# 48V_0_5A_Converter.net
KiCad netlist of a schematic drawn in Altium Designer
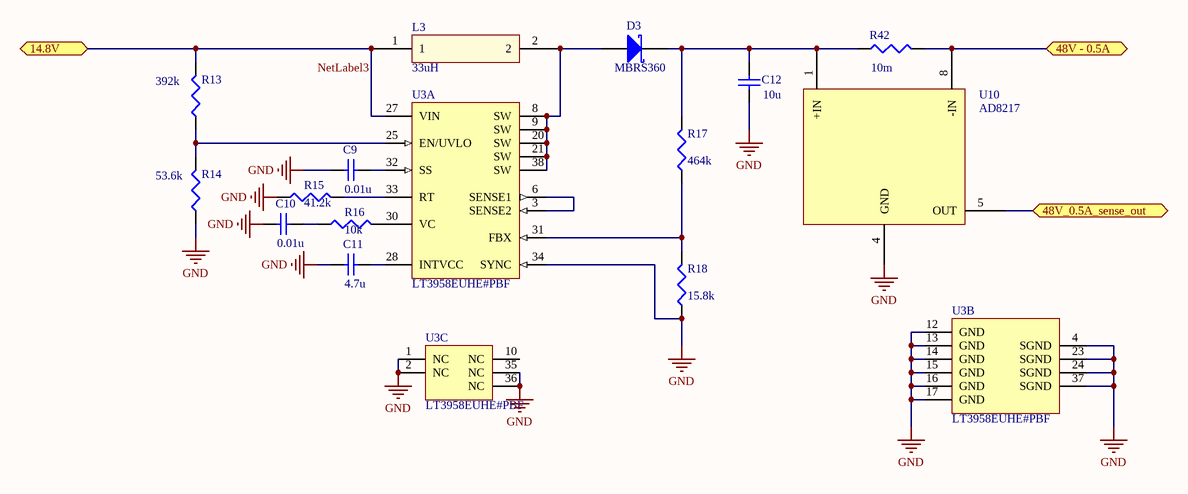
[diagram p0: 48V_0.5A_Converter.SchDoc]

(export (version "E")
  (design (tool "Eeschema 10.0.6"))
  (components
    (comp (ref "C9")
      (value "0.01u")
      (footprint "C1206")
      (description "Capacitor (Semiconductor SIM Model)")
      (fields (field (name "Comment") "Cap Semi") (field (name "PUBLISHER") "Altium Limited"))
      (libsource (lib "Miscellaneous Devices") (part "Cap Semi"))
    )
    (comp (ref "C10")
      (value "0.01u")
      (footprint "C1206")
      (description "Capacitor (Semiconductor SIM Model)")
      (fields (field (name "Comment") "Cap Semi") (field (name "PUBLISHER") "Altium Limited"))
      (libsource (lib "Miscellaneous Devices") (part "Cap Semi"))
    )
    (comp (ref "C11")
      (value "4.7u")
      (footprint "C1206")
      (description "Capacitor (Semiconductor SIM Model)")
      (fields (field (name "Comment") "Cap Semi") (field (name "PUBLISHER") "Altium Limited"))
      (libsource (lib "Miscellaneous Devices") (part "Cap Semi"))
    )
    (comp (ref "C12")
      (value "10u")
      (footprint "C1206")
      (description "Capacitor (Semiconductor SIM Model)")
      (fields (field (name "Comment") "Cap Semi") (field (name "PUBLISHER") "Altium Limited"))
      (libsource (lib "Miscellaneous Devices") (part "Cap Semi"))
    )
    (comp (ref "D3")
      (value "MBRS360")
      (footprint "SMB")
      (description "Schottky Diode")
      (fields (field (name "PUBLISHER") "Altium Limited"))
      (libsource (lib "Miscellaneous Devices") (part "D Schottky"))
    )
    (comp (ref "L3")
      (value "33uH")
      (footprint "INDP125125X45N")
      (description "33uH Inductors")
      (libsource (lib "IHLP-6767DZ-11") (part "IHLP-6767DZ-11"))
    )
    (comp (ref "R13")
      (value "392k")
      (footprint "J1-0603")
      (description "Resistor")
      (fields (field (name "Comment") "Res3") (field (name "PUBLISHER") "Altium Limited"))
      (libsource (lib "Miscellaneous Devices") (part "Res3"))
    )
    (comp (ref "R14")
      (value "53.6k")
      (footprint "J1-0603")
      (description "Resistor")
      (fields (field (name "Comment") "Res3") (field (name "PUBLISHER") "Altium Limited"))
      (libsource (lib "Miscellaneous Devices") (part "Res3"))
    )
    (comp (ref "R15")
      (value "41.2k")
      (footprint "J1-0603")
      (description "Resistor")
      (fields (field (name "Comment") "Res3") (field (name "PUBLISHER") "Altium Limited"))
      (libsource (lib "Miscellaneous Devices") (part "Res3"))
    )
    (comp (ref "R16")
      (value "10k")
      (footprint "J1-0603")
      (description "Resistor")
      (fields (field (name "Comment") "Res3") (field (name "PUBLISHER") "Altium Limited"))
      (libsource (lib "Miscellaneous Devices") (part "Res3"))
    )
    (comp (ref "R17")
      (value "464k")
      (footprint "J1-0603")
      (description "Resistor")
      (fields (field (name "Comment") "Res3") (field (name "PUBLISHER") "Altium Limited"))
      (libsource (lib "Miscellaneous Devices") (part "Res3"))
    )
    (comp (ref "R18")
      (value "15.8k")
      (footprint "J1-0603")
      (description "Resistor")
      (fields (field (name "Comment") "Res3") (field (name "PUBLISHER") "Altium Limited"))
      (libsource (lib "Miscellaneous Devices") (part "Res3"))
    )
    (comp (ref "R42")
      (value "10m")
      (footprint "J1-0603")
      (description "Resistor")
      (fields (field (name "Comment") "Res3") (field (name "PUBLISHER") "Altium Limited"))
      (libsource (lib "Miscellaneous Devices") (part "Res3"))
    )
    (comp (ref "U3")
      (value "LT3958EUHE#PBF")
      (footprint "LT-UHE-36-V-UHE28MA_V")
      (fields (field (name "MANUFACTURER") "Linear Technology"))
      (libsource (lib "Linear Technology Power Management Switching Regulator LT1074-LT8705") (part "LT3958EUHE#PBF"))
    )
    (comp (ref "U10")
      (value "AD8217")
      (footprint "TSOP65P490X110-8N")
      (description "Current Shunt Moniter")
      (libsource (lib "AD8217") (part "Component_1"))
    )
  )
  (nets
    (net (code "1") (name "/14.8V") (class "Default")
      (node (ref "L3") (pin "1") (pinfunction "1_1") (pintype "passive"))
      (node (ref "R13") (pin "2") (pinfunction "2_2") (pintype "passive"))
      (node (ref "U3") (pin "27") (pinfunction "VIN_27") (pintype "power_in"))
    )
    (net (code "2") (name "/48V - 0.5A") (class "Default")
      (node (ref "R42") (pin "2") (pinfunction "2_2") (pintype "passive"))
      (node (ref "U10") (pin "8") (pinfunction "-IN_8") (pintype "passive"))
    )
    (net (code "3") (name "/48V_0.5A_sense_out") (class "Default")
      (node (ref "U10") (pin "5") (pinfunction "OUT_5") (pintype "passive"))
    )
    (net (code "5") (name "GND") (class "Default")
      (node (ref "C10") (pin "1") (pinfunction "1_1") (pintype "passive"))
      (node (ref "C11") (pin "1") (pinfunction "1_1") (pintype "passive"))
      (node (ref "C12") (pin "1") (pinfunction "1_1") (pintype "passive"))
      (node (ref "C9") (pin "1") (pinfunction "1_1") (pintype "passive"))
      (node (ref "R14") (pin "1") (pinfunction "1_1") (pintype "passive"))
      (node (ref "R15") (pin "1") (pinfunction "1_1") (pintype "passive"))
      (node (ref "R18") (pin "1") (pinfunction "1_1") (pintype "passive"))
      (node (ref "U10") (pin "4") (pinfunction "GND_4") (pintype "passive"))
      (node (ref "U3") (pin "1") (pinfunction "NC_1") (pintype "passive"))
      (node (ref "U3") (pin "12") (pinfunction "GND_12") (pintype "power_in"))
      (node (ref "U3") (pin "13") (pinfunction "GND_13") (pintype "power_in"))
      (node (ref "U3") (pin "14") (pinfunction "GND_14") (pintype "power_in"))
      (node (ref "U3") (pin "15") (pinfunction "GND_15") (pintype "power_in"))
      (node (ref "U3") (pin "16") (pinfunction "GND_16") (pintype "power_in"))
      (node (ref "U3") (pin "17") (pinfunction "GND_17") (pintype "power_in"))
      (node (ref "U3") (pin "2") (pinfunction "NC_2") (pintype "passive"))
      (node (ref "U3") (pin "23") (pinfunction "SGND_23") (pintype "power_in"))
      (node (ref "U3") (pin "24") (pinfunction "SGND_24") (pintype "power_in"))
      (node (ref "U3") (pin "34") (pinfunction "SYNC_34") (pintype "input"))
      (node (ref "U3") (pin "35") (pinfunction "NC_35") (pintype "passive"))
      (node (ref "U3") (pin "36") (pinfunction "NC_36") (pintype "passive"))
      (node (ref "U3") (pin "37") (pinfunction "SGND_37") (pintype "power_in"))
      (node (ref "U3") (pin "4") (pinfunction "SGND_4") (pintype "power_in"))
    )
    (net (code "6") (name "Net-(C10-Pad2)") (class "Default")
      (node (ref "C10") (pin "2") (pinfunction "2_2") (pintype "passive"))
      (node (ref "R16") (pin "1") (pinfunction "1_1") (pintype "passive"))
    )
    (net (code "7") (name "Net-(D3-A)") (class "Default")
      (node (ref "D3") (pin "1") (pinfunction "A_1") (pintype "passive"))
      (node (ref "L3") (pin "2") (pinfunction "2_2") (pintype "passive"))
      (node (ref "U3") (pin "20") (pinfunction "SW_20") (pintype "power_in"))
      (node (ref "U3") (pin "21") (pinfunction "SW_21") (pintype "power_in"))
      (node (ref "U3") (pin "38") (pinfunction "SW_38") (pintype "power_in"))
      (node (ref "U3") (pin "8") (pinfunction "SW_8") (pintype "power_in"))
      (node (ref "U3") (pin "9") (pinfunction "SW_9") (pintype "power_in"))
    )
    (net (code "8") (name "Net-(D3-K)") (class "Default")
      (node (ref "C12") (pin "2") (pinfunction "2_2") (pintype "passive"))
      (node (ref "D3") (pin "2") (pinfunction "K_2") (pintype "passive"))
      (node (ref "R17") (pin "2") (pinfunction "2_2") (pintype "passive"))
      (node (ref "R42") (pin "1") (pinfunction "1_1") (pintype "passive"))
      (node (ref "U10") (pin "1") (pinfunction "+IN_1") (pintype "passive"))
    )
    (net (code "9") (name "Net-(U3A-EN{slash}UVLO)") (class "Default")
      (node (ref "R13") (pin "1") (pinfunction "1_1") (pintype "passive"))
      (node (ref "R14") (pin "2") (pinfunction "2_2") (pintype "passive"))
      (node (ref "U3") (pin "25") (pinfunction "EN/UVLO_25") (pintype "input"))
    )
    (net (code "10") (name "Net-(U3A-FBX)") (class "Default")
      (node (ref "R17") (pin "1") (pinfunction "1_1") (pintype "passive"))
      (node (ref "R18") (pin "2") (pinfunction "2_2") (pintype "passive"))
      (node (ref "U3") (pin "31") (pinfunction "FBX_31") (pintype "input"))
    )
    (net (code "11") (name "Net-(U3A-INTVCC)") (class "Default")
      (node (ref "C11") (pin "2") (pinfunction "2_2") (pintype "passive"))
      (node (ref "U3") (pin "28") (pinfunction "INTVCC_28") (pintype "power_in"))
    )
    (net (code "12") (name "Net-(U3A-RT)") (class "Default")
      (node (ref "R15") (pin "2") (pinfunction "2_2") (pintype "passive"))
      (node (ref "U3") (pin "33") (pinfunction "RT_33") (pintype "passive"))
    )
    (net (code "13") (name "Net-(U3A-SENSE1)") (class "Default")
      (node (ref "U3") (pin "3") (pinfunction "SENSE2_3") (pintype "input"))
      (node (ref "U3") (pin "6") (pinfunction "SENSE1_6") (pintype "output"))
    )
    (net (code "14") (name "Net-(U3A-SS)") (class "Default")
      (node (ref "C9") (pin "2") (pinfunction "2_2") (pintype "passive"))
      (node (ref "U3") (pin "32") (pinfunction "SS_32") (pintype "input"))
    )
    (net (code "15") (name "Net-(U3A-VC)") (class "Default")
      (node (ref "R16") (pin "2") (pinfunction "2_2") (pintype "passive"))
      (node (ref "U3") (pin "30") (pinfunction "VC_30") (pintype "passive"))
    )
    (net (code "16") (name "unconnected-(U3C-NC-Pad10)") (class "Default")
      (node (ref "U3") (pin "10") (pinfunction "NC_10") (pintype "passive"))
    )
  )
)
